# AdaptadorBateria.net
KiCad netlist of a schematic drawn in Altium Designer
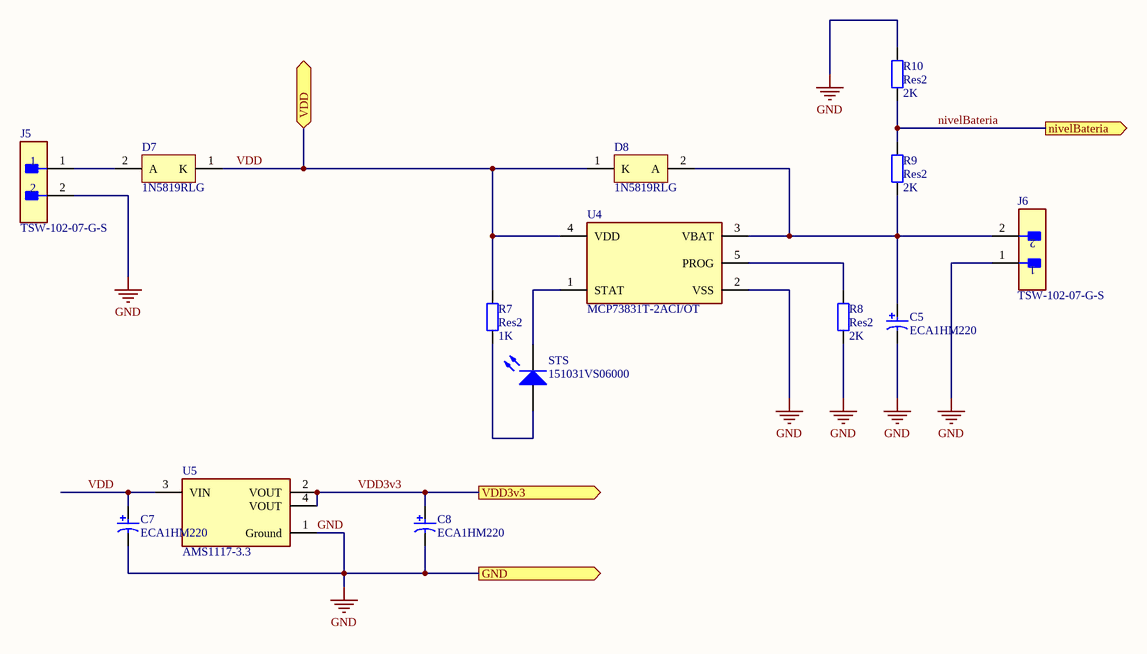
[diagram p0: AdaptadorBateria.SchDoc]

(export (version "E")
  (design (tool "Eeschema 10.0.6"))
  (components
    (comp (ref "C5")
      (value "ECA1HM220")
      (footprint "CAPPR55-200-1100X500X1200")
      (description "Aluminum Electrolytic Capacitor, 22 uF, +/- 20%, 50 V, -40 to 85 degC, 2-Pin THD, RoHS, Bulk")
      (fields (field (name "VOLTAGE") "50V") (field (name "MANUFACTURER") "Panasonic"))
      (libsource (lib "Altium Content Vault") (part "CAP-P-2"))
    )
    (comp (ref "C7")
      (value "ECA1HM220")
      (footprint "CAPPR55-200-1100X500X1200")
      (description "Aluminum Electrolytic Capacitor, 22 uF, +/- 20%, 50 V, -40 to 85 degC, 2-Pin THD, RoHS, Bulk")
      (fields (field (name "VOLTAGE") "50V") (field (name "MANUFACTURER") "Panasonic"))
      (libsource (lib "Altium Content Vault") (part "CAP-P-2"))
    )
    (comp (ref "C8")
      (value "ECA1HM220")
      (footprint "CAPPR55-200-1100X500X1200")
      (description "Aluminum Electrolytic Capacitor, 22 uF, +/- 20%, 50 V, -40 to 85 degC, 2-Pin THD, RoHS, Bulk")
      (fields (field (name "VOLTAGE") "50V") (field (name "MANUFACTURER") "Panasonic"))
      (libsource (lib "Altium Content Vault") (part "CAP-P-2"))
    )
    (comp (ref "D7")
      (value "1N5819RLG")
      (footprint "ONSC-AXIAL_LEAD-2-59-10_P")
      (description "Rectifier, 2-Pin Axial_Lead, Pb-Free, Tape and Reel")
      (fields (field (name "MANUFACTURER") "On Semiconductor"))
      (libsource (lib "") (part "ONSC-D-K1A2-2_A_1"))
    )
    (comp (ref "D8")
      (value "1N5819RLG")
      (footprint "ONSC-AXIAL_LEAD-2-59-10_P")
      (description "Rectifier, 2-Pin Axial_Lead, Pb-Free, Tape and Reel")
      (fields (field (name "MANUFACTURER") "On Semiconductor"))
      (libsource (lib "Altium Content Vault") (part "ONSC-D-K1A2-2_A"))
    )
    (comp (ref "J5")
      (value "TSW-102-07-G-S")
      (footprint "FP-TSW-102-07-G-S-MFG")
      (description "CONN HEADER VERT 2POS 2.54MM")
      (fields
        (field (name "MANUFACTURER") "Samtec")
        (field (name "OCTOPART") "https://octopart.com/tsw-102-07-g-s-samtec-272197")
      )
      (libsource (lib "Altium Content Vault") (part "3bc925449376181038e59eaffc5286c"))
    )
    (comp (ref "J6")
      (value "TSW-102-07-G-S")
      (footprint "FP-TSW-102-07-G-S-MFG")
      (description "CONN HEADER VERT 2POS 2.54MM")
      (fields
        (field (name "MANUFACTURER") "Samtec")
        (field (name "OCTOPART") "https://octopart.com/tsw-102-07-g-s-samtec-272197")
      )
      (libsource (lib "") (part "3bc925449376181038e59eaffc5286c_1"))
    )
    (comp (ref "R7")
      (value "Res2")
      (footprint "AXIAL-0.4")
      (description "Resistor")
      (fields (field (name "ALTIUM_VALUE") "1K") (field (name "PUBLISHER") "Altium Limited"))
      (libsource (lib "Miscellaneous Devices") (part "Res2"))
    )
    (comp (ref "R8")
      (value "Res2")
      (footprint "AXIAL-0.4")
      (description "Resistor")
      (fields (field (name "ALTIUM_VALUE") "2K") (field (name "PUBLISHER") "Altium Limited"))
      (libsource (lib "Miscellaneous Devices") (part "Res2"))
    )
    (comp (ref "R9")
      (value "Res2")
      (footprint "AXIAL-0.4")
      (description "Resistor")
      (fields (field (name "ALTIUM_VALUE") "2K") (field (name "PUBLISHER") "Altium Limited"))
      (libsource (lib "Miscellaneous Devices") (part "Res2"))
    )
    (comp (ref "R10")
      (value "Res2")
      (footprint "AXIAL-0.4")
      (description "Resistor")
      (fields (field (name "ALTIUM_VALUE") "2K") (field (name "PUBLISHER") "Altium Limited"))
      (libsource (lib "Miscellaneous Devices") (part "Res2"))
    )
    (comp (ref "STS")
      (value "151031VS06000")
      (footprint "Type 3mm")
      (description "THT LED round mono-color color lens, WL-TMRC , Bright Green")
      (fields (field (name "MANUFACTURER") "Wuerth Elektronik"))
      (libsource (lib "Altium Content Vault") (part "WE-LED_K1A2-2"))
    )
    (comp (ref "U4")
      (value "MCP73831T-2ACI/OT")
      (footprint "FP-C04-091-OT-IPC_B")
      (description "IC CONTROLLR LI-ION 4.2V SOT23-5")
      (libsource (lib "Altium Content Vault") (part "61f5a3bb3429d9e0caadea342aa3b19"))
    )
    (comp (ref "U5")
      (value "AMS1117-3.3")
      (footprint "FP-AMS1117-IPC_C")
      (description "LDO Voltage Regulators 1A, 3.3V")
      (fields
        (field (name "OCTOPART") "https://octopart.com/ams1117-3.3-advanced+monolithic+systems-25899300")
        (field (name "MANUFACTURER") "Advanced Monolithic Systems")
      )
      (libsource (lib "Altium Content Vault") (part "8bdbb5f8e77002000e30dd2845d0354"))
    )
  )
  (nets
    (net (code "1") (name "/VDD") (class "Default")
      (node (ref "C7") (pin "1") (pinfunction "1_1") (pintype "passive"))
      (node (ref "D7") (pin "1") (pinfunction "K_1") (pintype "passive"))
      (node (ref "D8") (pin "1") (pinfunction "K_1") (pintype "passive"))
      (node (ref "R7") (pin "2") (pinfunction "2_2") (pintype "passive"))
      (node (ref "U4") (pin "4") (pinfunction "VDD_4") (pintype "power_in"))
      (node (ref "U5") (pin "3") (pinfunction "VIN_3") (pintype "power_in"))
    )
    (net (code "2") (name "/VDD3v3") (class "Default")
      (node (ref "C8") (pin "1") (pinfunction "1_1") (pintype "passive"))
      (node (ref "U5") (pin "2") (pinfunction "VOUT_2") (pintype "passive"))
      (node (ref "U5") (pin "4") (pinfunction "VOUT_4") (pintype "passive"))
    )
    (net (code "3") (name "/nivelBateria") (class "Default")
      (node (ref "R10") (pin "1") (pinfunction "1_1") (pintype "passive"))
      (node (ref "R9") (pin "2") (pinfunction "2_2") (pintype "passive"))
    )
    (net (code "4") (name "GND") (class "Default")
      (node (ref "C5") (pin "2") (pinfunction "2_2") (pintype "passive"))
      (node (ref "C7") (pin "2") (pinfunction "2_2") (pintype "passive"))
      (node (ref "C8") (pin "2") (pinfunction "2_2") (pintype "passive"))
      (node (ref "J5") (pin "2") (pinfunction "2_2") (pintype "passive"))
      (node (ref "J6") (pin "1") (pinfunction "1_1") (pintype "passive"))
      (node (ref "R10") (pin "2") (pinfunction "2_2") (pintype "passive"))
      (node (ref "R8") (pin "1") (pinfunction "1_1") (pintype "passive"))
      (node (ref "U4") (pin "2") (pinfunction "VSS_2") (pintype "power_in"))
      (node (ref "U5") (pin "1") (pinfunction "Ground_1") (pintype "power_in"))
    )
    (net (code "5") (name "Net-(D7-A)") (class "Default")
      (node (ref "D7") (pin "2") (pinfunction "A_2") (pintype "passive"))
      (node (ref "J5") (pin "1") (pinfunction "1_1") (pintype "passive"))
    )
    (net (code "6") (name "Net-(D8-A)") (class "Default")
      (node (ref "C5") (pin "1") (pinfunction "1_1") (pintype "passive"))
      (node (ref "D8") (pin "2") (pinfunction "A_2") (pintype "passive"))
      (node (ref "J6") (pin "2") (pinfunction "2_2") (pintype "passive"))
      (node (ref "R9") (pin "1") (pinfunction "1_1") (pintype "passive"))
      (node (ref "U4") (pin "3") (pinfunction "VBAT_3") (pintype "power_in"))
    )
    (net (code "7") (name "Net-(STS-A)") (class "Default")
      (node (ref "R7") (pin "1") (pinfunction "1_1") (pintype "passive"))
      (node (ref "STS") (pin "2") (pinfunction "A_2") (pintype "passive"))
    )
    (net (code "8") (name "Net-(STS-K)") (class "Default")
      (node (ref "STS") (pin "1") (pinfunction "K_1") (pintype "passive"))
      (node (ref "U4") (pin "1") (pinfunction "STAT_1") (pintype "passive"))
    )
    (net (code "9") (name "Net-(U4-PROG)") (class "Default")
      (node (ref "R8") (pin "2") (pinfunction "2_2") (pintype "passive"))
      (node (ref "U4") (pin "5") (pinfunction "PROG_5") (pintype "passive"))
    )
  )
)
